# BMS_CAN.net
KiCad netlist of a schematic drawn in Altium Designer
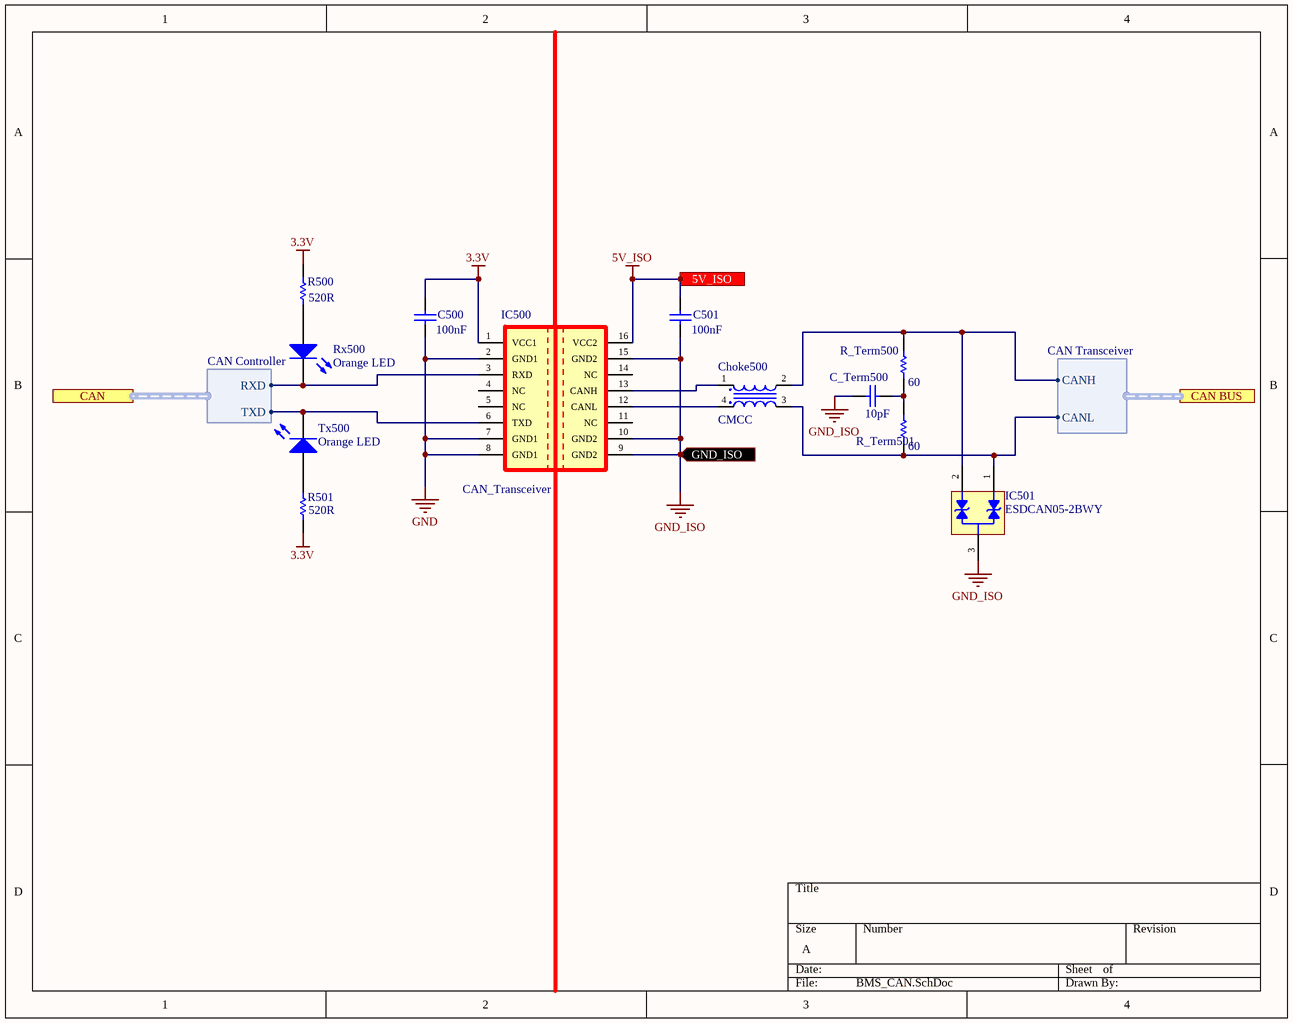
[diagram p0: BMS_CAN.SchDoc]

(export (version "E")
  (design (tool "Eeschema 10.0.6"))
  (components
    (comp (ref "C500")
      (value "100nF")
      (footprint "CAPC2012X14N")
      (description "Capacitor")
      (fields (field (name "Comment") "Cap") (field (name "PUBLISHER") "Altium Limited"))
      (libsource (lib "Miscellaneous Devices") (part "Cap"))
    )
    (comp (ref "C501")
      (value "100nF")
      (footprint "CAPC2012X14N")
      (description "Capacitor")
      (fields (field (name "Comment") "Cap") (field (name "PUBLISHER") "Altium Limited"))
      (libsource (lib "Miscellaneous Devices") (part "Cap"))
    )
    (comp (ref "Choke500")
      (value "CMCC")
      (footprint "DLW32SH101XK2L")
      (description "Common Mode Chokes / Filters 1210 80VDC 100uH 150mA AEC-Q200")
      (libsource (lib "DLW32SH101XK2L") (part "DLW32SH101XK2L"))
    )
    (comp (ref "C_Term500")
      (value "10pF")
      (footprint "CAPC2012X14N")
      (description "Capacitor")
      (fields (field (name "Comment") "Cap") (field (name "PUBLISHER") "Altium Limited"))
      (libsource (lib "Miscellaneous Devices") (part "Cap"))
    )
    (comp (ref "IC500")
      (value "CAN_Transceiver")
      (footprint "SOIC127P1030X265-16N")
      (description "Digital Isolators Isolated 5V CAN Xcvr")
      (libsource (lib "CAN_Transceiver") (part "ISO1050DWR"))
    )
    (comp (ref "IC501")
      (value "ESDCAN05-2BWY")
      (footprint "SOT70P210X110-3N")
      (description "Automotive dual-line TVS in SOT323-3L for CAN bus")
      (libsource (lib "ESDCAN05-2BWY") (part "ESDCAN05-2BWY"))
    )
    (comp (ref "R500")
      (value "520R")
      (footprint "RESC2012X07N")
      (description "Resistor")
      (fields (field (name "Comment") "Res1") (field (name "PUBLISHER") "Altium Limited"))
      (libsource (lib "Miscellaneous Devices") (part "Res1"))
    )
    (comp (ref "R501")
      (value "520R")
      (footprint "RESC2012X07N")
      (description "Resistor")
      (fields (field (name "Comment") "Res1") (field (name "PUBLISHER") "Altium Limited"))
      (libsource (lib "Miscellaneous Devices") (part "Res1"))
    )
    (comp (ref "Rx500")
      (value "Orange LED")
      (footprint "SMD ORANGE LED")
      (description "Typical INFRARED GaAs LED")
      (fields (field (name "PUBLISHER") "Altium Limited"))
      (libsource (lib "Miscellaneous Devices") (part "LED0"))
    )
    (comp (ref "R_Term500")
      (value "60")
      (footprint "RESC2012X07N")
      (description "Resistor")
      (fields (field (name "Comment") "Res1") (field (name "PUBLISHER") "Altium Limited"))
      (libsource (lib "Miscellaneous Devices") (part "Res1"))
    )
    (comp (ref "R_Term501")
      (value "60")
      (footprint "RESC2012X07N")
      (description "Resistor")
      (fields (field (name "Comment") "Res1") (field (name "PUBLISHER") "Altium Limited"))
      (libsource (lib "Miscellaneous Devices") (part "Res1"))
    )
    (comp (ref "Tx500")
      (value "Orange LED")
      (footprint "SMD ORANGE LED")
      (description "Typical INFRARED GaAs LED")
      (fields (field (name "PUBLISHER") "Altium Limited"))
      (libsource (lib "Miscellaneous Devices") (part "LED0"))
    )
  )
  (nets
    (net (code "6") (name "3.3V") (class "Default")
      (node (ref "C500") (pin "2") (pinfunction "2_2") (pintype "passive"))
      (node (ref "IC500") (pin "1") (pinfunction "VCC1_1") (pintype "passive"))
      (node (ref "R500") (pin "2") (pinfunction "2_2") (pintype "passive"))
      (node (ref "R501") (pin "2") (pinfunction "2_2") (pintype "passive"))
    )
    (net (code "7") (name "5V_ISO") (class "Default")
      (node (ref "C501") (pin "2") (pinfunction "2_2") (pintype "passive"))
      (node (ref "IC500") (pin "16") (pinfunction "VCC2_16") (pintype "passive"))
    )
    (net (code "8") (name "GND") (class "Default")
      (node (ref "C500") (pin "1") (pinfunction "1_1") (pintype "passive"))
      (node (ref "IC500") (pin "2") (pinfunction "GND1_2") (pintype "passive"))
      (node (ref "IC500") (pin "7") (pinfunction "GND1_7") (pintype "passive"))
      (node (ref "IC500") (pin "8") (pinfunction "GND1_8") (pintype "passive"))
    )
    (net (code "9") (name "GND_ISO") (class "Default")
      (node (ref "C501") (pin "1") (pinfunction "1_1") (pintype "passive"))
      (node (ref "C_Term500") (pin "2") (pinfunction "2_2") (pintype "passive"))
      (node (ref "IC500") (pin "10") (pinfunction "GND2_10") (pintype "passive"))
      (node (ref "IC500") (pin "15") (pinfunction "GND2_15") (pintype "passive"))
      (node (ref "IC500") (pin "9") (pinfunction "GND2_9") (pintype "passive"))
      (node (ref "IC501") (pin "3") (pinfunction "3_3") (pintype "passive"))
    )
    (net (code "10") (name "Net-(C_Term500-Pad1)") (class "Default")
      (node (ref "C_Term500") (pin "1") (pinfunction "1_1") (pintype "passive"))
      (node (ref "R_Term500") (pin "1") (pinfunction "1_1") (pintype "passive"))
      (node (ref "R_Term501") (pin "2") (pinfunction "2_2") (pintype "passive"))
    )
    (net (code "11") (name "Net-(Choke500-Pad2)") (class "Default")
      (node (ref "Choke500") (pin "2") (pinfunction "2_2") (pintype "passive"))
      (node (ref "IC501") (pin "2") (pinfunction "2_2") (pintype "passive"))
      (node (ref "R_Term500") (pin "2") (pinfunction "2_2") (pintype "passive"))
    )
    (net (code "12") (name "Net-(Choke500-Pad3)") (class "Default")
      (node (ref "Choke500") (pin "3") (pinfunction "3_3") (pintype "passive"))
      (node (ref "IC501") (pin "1") (pinfunction "1_1") (pintype "passive"))
      (node (ref "R_Term501") (pin "1") (pinfunction "1_1") (pintype "passive"))
    )
    (net (code "13") (name "Net-(IC500-CANH)") (class "Default")
      (node (ref "Choke500") (pin "1") (pinfunction "1_1") (pintype "passive"))
      (node (ref "IC500") (pin "13") (pinfunction "CANH_13") (pintype "passive"))
    )
    (net (code "14") (name "Net-(IC500-CANL)") (class "Default")
      (node (ref "Choke500") (pin "4") (pinfunction "4_4") (pintype "passive"))
      (node (ref "IC500") (pin "12") (pinfunction "CANL_12") (pintype "passive"))
    )
    (net (code "15") (name "Net-(IC500-RXD)") (class "Default")
      (node (ref "IC500") (pin "3") (pinfunction "RXD_3") (pintype "passive"))
      (node (ref "Rx500") (pin "2") (pinfunction "K_2") (pintype "passive"))
    )
    (net (code "16") (name "Net-(IC500-TXD)") (class "Default")
      (node (ref "IC500") (pin "6") (pinfunction "TXD_6") (pintype "passive"))
      (node (ref "Tx500") (pin "2") (pinfunction "K_2") (pintype "passive"))
    )
    (net (code "17") (name "Net-(Rx500-A)") (class "Default")
      (node (ref "R500") (pin "1") (pinfunction "1_1") (pintype "passive"))
      (node (ref "Rx500") (pin "1") (pinfunction "A_1") (pintype "passive"))
    )
    (net (code "18") (name "Net-(Tx500-A)") (class "Default")
      (node (ref "R501") (pin "1") (pinfunction "1_1") (pintype "passive"))
      (node (ref "Tx500") (pin "1") (pinfunction "A_1") (pintype "passive"))
    )
    (net (code "19") (name "unconnected-(IC500-NC-Pad4)") (class "Default")
      (node (ref "IC500") (pin "4") (pinfunction "NC_4") (pintype "passive"))
    )
    (net (code "20") (name "unconnected-(IC500-NC-Pad5)") (class "Default")
      (node (ref "IC500") (pin "5") (pinfunction "NC_5") (pintype "passive"))
    )
    (net (code "21") (name "unconnected-(IC500-NC-Pad11)") (class "Default")
      (node (ref "IC500") (pin "11") (pinfunction "NC_11") (pintype "passive"))
    )
    (net (code "22") (name "unconnected-(IC500-NC-Pad14)") (class "Default")
      (node (ref "IC500") (pin "14") (pinfunction "NC_14") (pintype "passive"))
    )
  )
)
